# au-ar.net
KiCad netlist of a schematic drawn in EAGLE
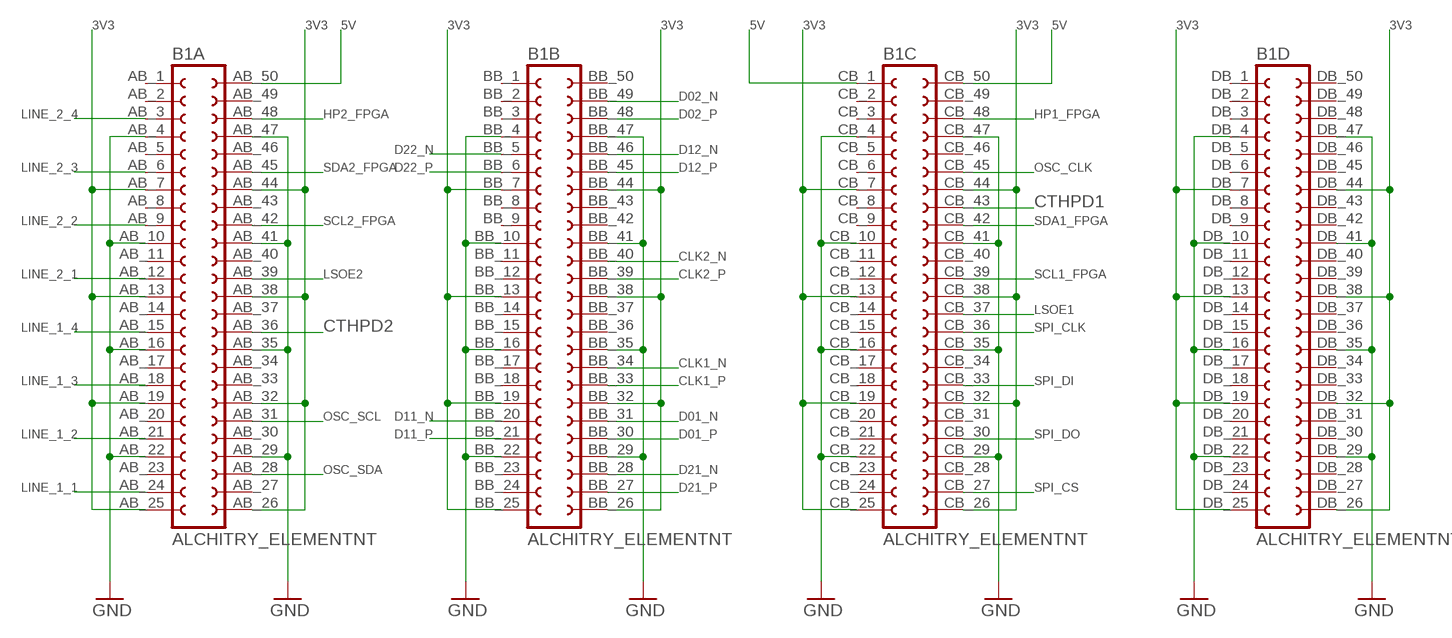
[diagram p0: schematic, sheet 1]
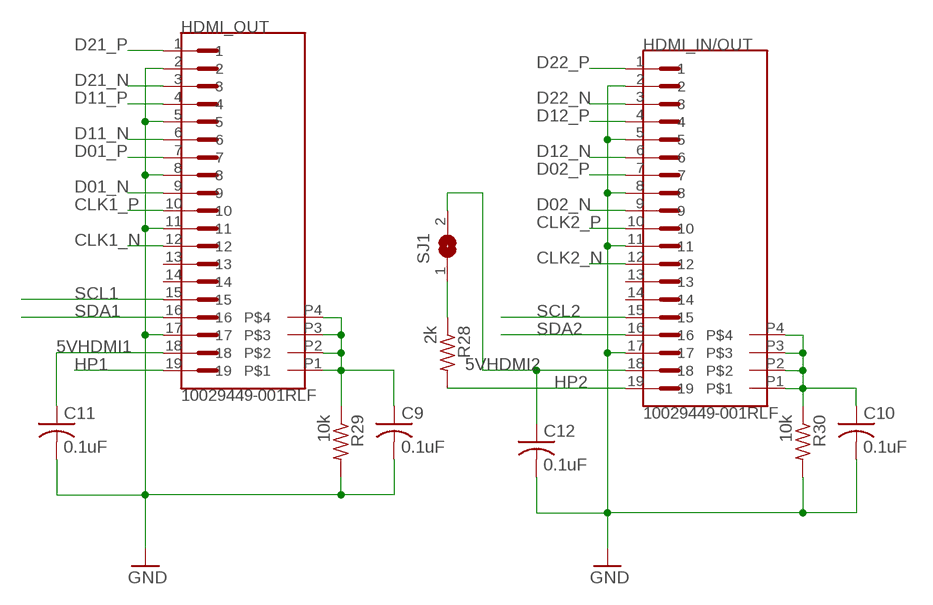
[diagram p1: schematic, sheet 2]
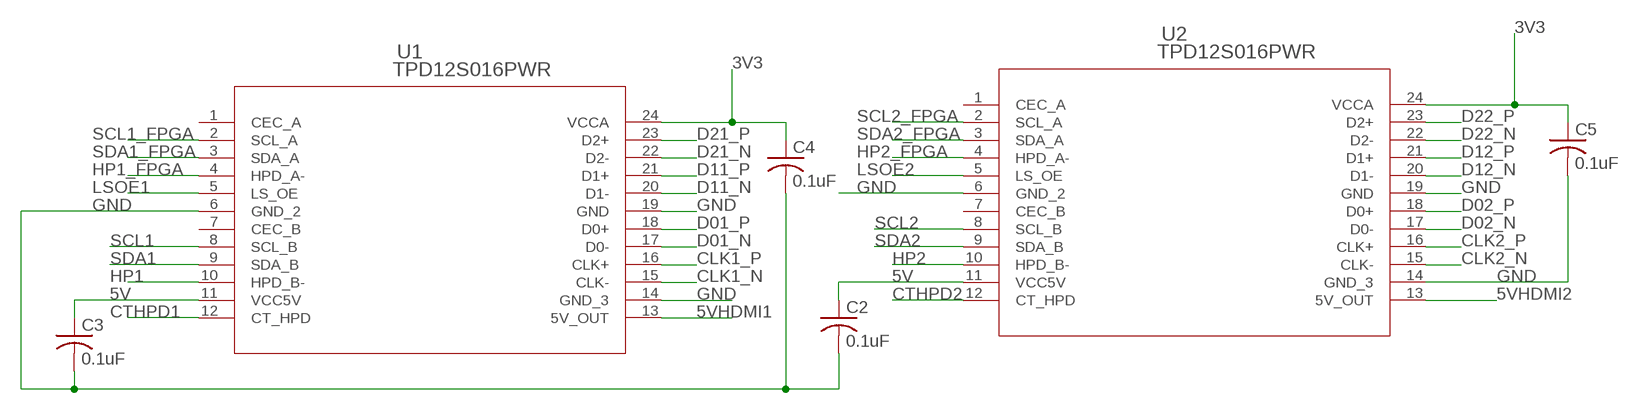
[diagram p2: schematic, sheet 3]
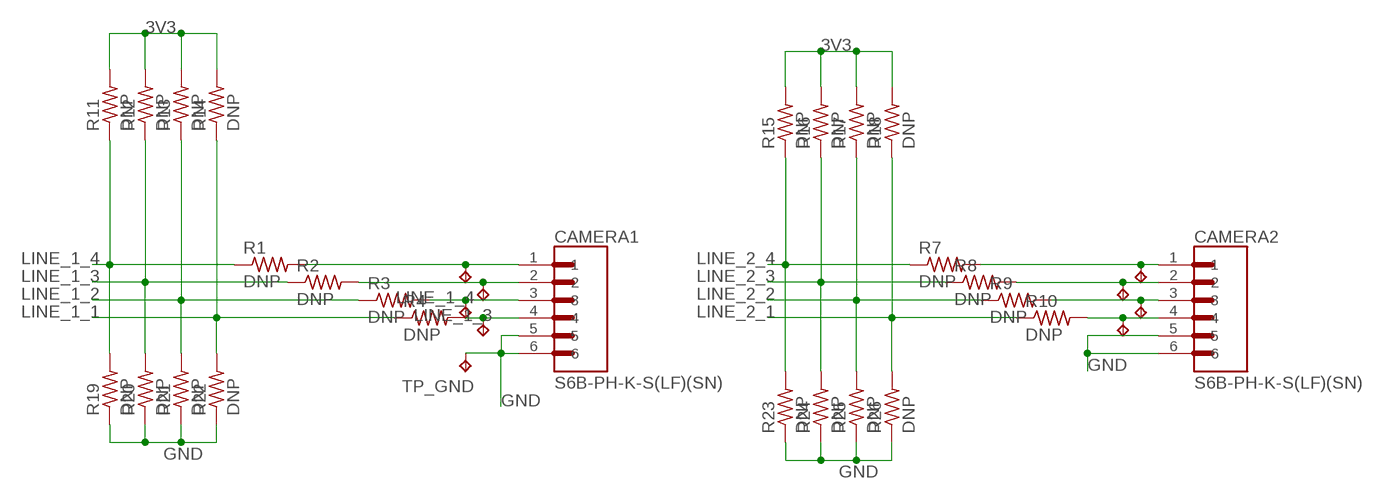
[diagram p3: schematic, sheet 4]
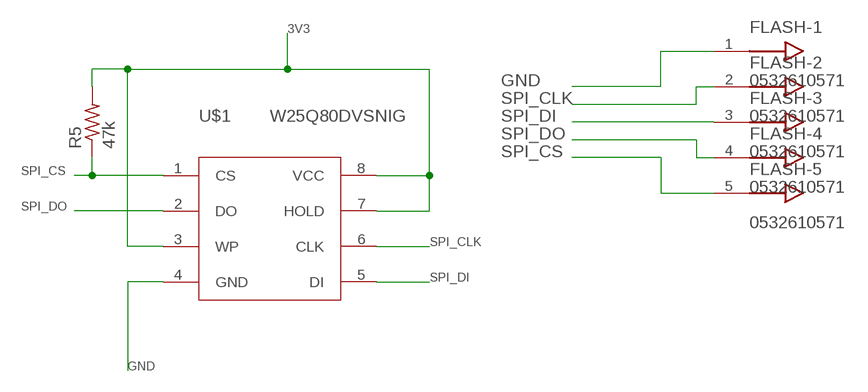
[diagram p4: schematic, sheet 5]
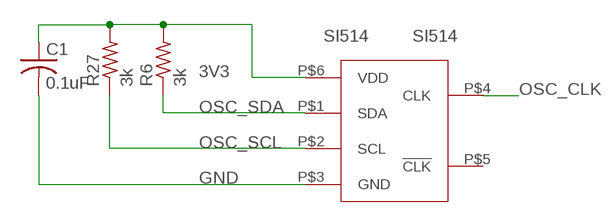
[diagram p5: schematic, sheet 6]

(export (version "E")
  (design (tool "Eeschema 10.0.6"))
  (components
    (comp (ref "C1")
      (value "0.1uF")
      (footprint "eagle-import:C0603")
      (libsource (lib "eagle-import") (part "C-USC0603"))
    )
    (comp (ref "R6")
      (value "3k")
      (footprint "eagle-import:R0603")
      (libsource (lib "eagle-import") (part "R-US_R0603"))
    )
    (comp (ref "R27")
      (value "3k")
      (footprint "eagle-import:R0603")
      (libsource (lib "eagle-import") (part "R-US_R0603"))
    )
    (comp (ref "SI514")
      (value "SI514")
      (footprint "eagle-import:XTAL-6PIN")
      (libsource (lib "eagle-import") (part "SI514"))
    )
    (comp (ref "FLASH")
      (value "0532610571")
      (footprint "eagle-import:PICOBLADE53261-0571")
      (fields (field (name "MANUFACTURER") "Molex Inc"))
      (libsource (lib "eagle-import") (part "0532610571"))
    )
    (comp (ref "R5")
      (value "47k")
      (footprint "eagle-import:R0603")
      (libsource (lib "eagle-import") (part "R-US_R0603"))
    )
    (comp (ref "U$1")
      (value "W25Q80DVSNIG")
      (footprint "eagle-import:SOIC8")
      (libsource (lib "eagle-import") (part "W25Q80DVSNIG"))
    )
    (comp (ref "C9")
      (value "0.1uF")
      (footprint "eagle-import:C0603")
      (libsource (lib "eagle-import") (part "C-USC0603"))
    )
    (comp (ref "C10")
      (value "0.1uF")
      (footprint "eagle-import:C0603")
      (libsource (lib "eagle-import") (part "C-USC0603"))
    )
    (comp (ref "C11")
      (value "0.1uF")
      (footprint "eagle-import:C0603")
      (libsource (lib "eagle-import") (part "C-USC0603"))
    )
    (comp (ref "C12")
      (value "0.1uF")
      (footprint "eagle-import:C0603")
      (libsource (lib "eagle-import") (part "C-USC0603"))
    )
    (comp (ref "HDMI_IN/OUT")
      (value "10029449-001RLF")
      (footprint "eagle-import:FCI_10029449-001RLF")
      (fields (field (name "MF") "Amphenol FCI"))
      (libsource (lib "eagle-import") (part "10029449-001RLF"))
    )
    (comp (ref "HDMI_OUT")
      (value "10029449-001RLF")
      (footprint "eagle-import:FCI_10029449-001RLF")
      (fields (field (name "MF") "Amphenol FCI"))
      (libsource (lib "eagle-import") (part "10029449-001RLF"))
    )
    (comp (ref "R28")
      (value "2k")
      (footprint "eagle-import:R0603")
      (libsource (lib "eagle-import") (part "R-US_R0603"))
    )
    (comp (ref "R29")
      (value "10k")
      (footprint "eagle-import:R0603")
      (libsource (lib "eagle-import") (part "R-US_R0603"))
    )
    (comp (ref "R30")
      (value "10k")
      (footprint "eagle-import:R0603")
      (libsource (lib "eagle-import") (part "R-US_R0603"))
    )
    (comp (ref "SJ1") (value "SJ") (footprint "eagle-import:SJ") (libsource (lib "eagle-import") (part "SJ")))
    (comp (ref "C2")
      (value "0.1uF")
      (footprint "eagle-import:C0603")
      (libsource (lib "eagle-import") (part "C-USC0603"))
    )
    (comp (ref "C3")
      (value "0.1uF")
      (footprint "eagle-import:C0603")
      (libsource (lib "eagle-import") (part "C-USC0603"))
    )
    (comp (ref "C4")
      (value "0.1uF")
      (footprint "eagle-import:C0603")
      (libsource (lib "eagle-import") (part "C-USC0603"))
    )
    (comp (ref "C5")
      (value "0.1uF")
      (footprint "eagle-import:C0603")
      (libsource (lib "eagle-import") (part "C-USC0603"))
    )
    (comp (ref "U1")
      (value "TPD12S016PWR")
      (footprint "eagle-import:PW24")
      (libsource (lib "eagle-import") (part "TPD12S016PWR"))
    )
    (comp (ref "U2")
      (value "TPD12S016PWR")
      (footprint "eagle-import:PW24")
      (libsource (lib "eagle-import") (part "TPD12S016PWR"))
    )
    (comp (ref "1")
      (value "LINE_1")
      (footprint "eagle-import:TP16R")
      (libsource (lib "eagle-import") (part "TPTP16R"))
    )
    (comp (ref "2")
      (value "LINE_2")
      (footprint "eagle-import:TP16R")
      (libsource (lib "eagle-import") (part "TPTP16R"))
    )
    (comp (ref "3")
      (value "LINE_3")
      (footprint "eagle-import:TP16R")
      (libsource (lib "eagle-import") (part "TPTP16R"))
    )
    (comp (ref "4")
      (value "LINE_1")
      (footprint "eagle-import:TP16R")
      (libsource (lib "eagle-import") (part "TPTP16R"))
    )
    (comp (ref "CAMERA1")
      (value "S6B-PH-K-S(LF)(SN)")
      (footprint "eagle-import:JST_S6B-PH-K-S(LF)(SN)")
      (fields
        (field (name "DIGI-KEY_PART_NUMBER") "455-1723-ND")
        (field (name "MF") "JST Sales")
        (field (name "MP") "S6B-PH-K-S_LF__SN_")
      )
      (libsource (lib "eagle-import") (part "S6B-PH-K-S(LF)(SN)"))
    )
    (comp (ref "CAMERA2")
      (value "S6B-PH-K-S(LF)(SN)")
      (footprint "eagle-import:JST_S6B-PH-K-S(LF)(SN)")
      (fields
        (field (name "DIGI-KEY_PART_NUMBER") "455-1723-ND")
        (field (name "MF") "JST Sales")
        (field (name "MP") "S6B-PH-K-S_LF__SN_")
      )
      (libsource (lib "eagle-import") (part "S6B-PH-K-S(LF)(SN)"))
    )
    (comp (ref "LINE_1_1")
      (value "TPTP16R")
      (footprint "eagle-import:TP16R")
      (libsource (lib "eagle-import") (part "TPTP16R"))
    )
    (comp (ref "LINE_1_2")
      (value "TPTP16R")
      (footprint "eagle-import:TP16R")
      (libsource (lib "eagle-import") (part "TPTP16R"))
    )
    (comp (ref "LINE_1_3")
      (value "TPTP16R")
      (footprint "eagle-import:TP16R")
      (libsource (lib "eagle-import") (part "TPTP16R"))
    )
    (comp (ref "LINE_1_4")
      (value "TPTP16R")
      (footprint "eagle-import:TP16R")
      (libsource (lib "eagle-import") (part "TPTP16R"))
    )
    (comp (ref "R1")
      (value "DNP")
      (footprint "eagle-import:R0603")
      (libsource (lib "eagle-import") (part "R-US_R0603"))
    )
    (comp (ref "R2")
      (value "DNP")
      (footprint "eagle-import:R0603")
      (libsource (lib "eagle-import") (part "R-US_R0603"))
    )
    (comp (ref "R3")
      (value "DNP")
      (footprint "eagle-import:R0603")
      (libsource (lib "eagle-import") (part "R-US_R0603"))
    )
    (comp (ref "R4")
      (value "DNP")
      (footprint "eagle-import:R0603")
      (libsource (lib "eagle-import") (part "R-US_R0603"))
    )
    (comp (ref "R7")
      (value "DNP")
      (footprint "eagle-import:R0603")
      (libsource (lib "eagle-import") (part "R-US_R0603"))
    )
    (comp (ref "R8")
      (value "DNP")
      (footprint "eagle-import:R0603")
      (libsource (lib "eagle-import") (part "R-US_R0603"))
    )
    (comp (ref "R9")
      (value "DNP")
      (footprint "eagle-import:R0603")
      (libsource (lib "eagle-import") (part "R-US_R0603"))
    )
    (comp (ref "R10")
      (value "DNP")
      (footprint "eagle-import:R0603")
      (libsource (lib "eagle-import") (part "R-US_R0603"))
    )
    (comp (ref "R11")
      (value "DNP")
      (footprint "eagle-import:R0603")
      (libsource (lib "eagle-import") (part "R-US_R0603"))
    )
    (comp (ref "R12")
      (value "DNP")
      (footprint "eagle-import:R0603")
      (libsource (lib "eagle-import") (part "R-US_R0603"))
    )
    (comp (ref "R13")
      (value "DNP")
      (footprint "eagle-import:R0603")
      (libsource (lib "eagle-import") (part "R-US_R0603"))
    )
    (comp (ref "R14")
      (value "DNP")
      (footprint "eagle-import:R0603")
      (libsource (lib "eagle-import") (part "R-US_R0603"))
    )
    (comp (ref "R15")
      (value "DNP")
      (footprint "eagle-import:R0603")
      (libsource (lib "eagle-import") (part "R-US_R0603"))
    )
    (comp (ref "R16")
      (value "DNP")
      (footprint "eagle-import:R0603")
      (libsource (lib "eagle-import") (part "R-US_R0603"))
    )
    (comp (ref "R17")
      (value "DNP")
      (footprint "eagle-import:R0603")
      (libsource (lib "eagle-import") (part "R-US_R0603"))
    )
    (comp (ref "R18")
      (value "DNP")
      (footprint "eagle-import:R0603")
      (libsource (lib "eagle-import") (part "R-US_R0603"))
    )
    (comp (ref "R19")
      (value "DNP")
      (footprint "eagle-import:R0603")
      (libsource (lib "eagle-import") (part "R-US_R0603"))
    )
    (comp (ref "R20")
      (value "DNP")
      (footprint "eagle-import:R0603")
      (libsource (lib "eagle-import") (part "R-US_R0603"))
    )
    (comp (ref "R21")
      (value "DNP")
      (footprint "eagle-import:R0603")
      (libsource (lib "eagle-import") (part "R-US_R0603"))
    )
    (comp (ref "R22")
      (value "DNP")
      (footprint "eagle-import:R0603")
      (libsource (lib "eagle-import") (part "R-US_R0603"))
    )
    (comp (ref "R23")
      (value "DNP")
      (footprint "eagle-import:R0603")
      (libsource (lib "eagle-import") (part "R-US_R0603"))
    )
    (comp (ref "R24")
      (value "DNP")
      (footprint "eagle-import:R0603")
      (libsource (lib "eagle-import") (part "R-US_R0603"))
    )
    (comp (ref "R25")
      (value "DNP")
      (footprint "eagle-import:R0603")
      (libsource (lib "eagle-import") (part "R-US_R0603"))
    )
    (comp (ref "R26")
      (value "DNP")
      (footprint "eagle-import:R0603")
      (libsource (lib "eagle-import") (part "R-US_R0603"))
    )
    (comp (ref "TP_GND")
      (value "TPTP16R")
      (footprint "eagle-import:TP16R")
      (libsource (lib "eagle-import") (part "TPTP16R"))
    )
    (comp (ref "B1")
      (value "ALCHITRY_ELEMENTNT")
      (footprint "eagle-import:ELEMENT_NO_TOP")
      (libsource (lib "eagle-import") (part "ALCHITRY_ELEMENTNT"))
    )
  )
  (nets
    (net (code "1") (name "3V3") (class "Default")
      (node (ref "B1") (pin "AB_13") (pinfunction "13_AB_13") (pintype "passive"))
      (node (ref "B1") (pin "AB_19") (pinfunction "19_AB_19") (pintype "passive"))
      (node (ref "B1") (pin "AB_25") (pinfunction "25_AB_25") (pintype "passive"))
      (node (ref "B1") (pin "AB_26") (pinfunction "26_AB_26") (pintype "passive"))
      (node (ref "B1") (pin "AB_32") (pinfunction "32_AB_32") (pintype "passive"))
      (node (ref "B1") (pin "AB_38") (pinfunction "38_AB_38") (pintype "passive"))
      (node (ref "B1") (pin "AB_44") (pinfunction "44_AB_44") (pintype "passive"))
      (node (ref "B1") (pin "AB_7") (pinfunction "7_AB_7") (pintype "passive"))
      (node (ref "B1") (pin "BB_13") (pinfunction "13_BB_13") (pintype "passive"))
      (node (ref "B1") (pin "BB_19") (pinfunction "19_BB_19") (pintype "passive"))
      (node (ref "B1") (pin "BB_25") (pinfunction "25_BB_25") (pintype "passive"))
      (node (ref "B1") (pin "BB_26") (pinfunction "26_BB_26") (pintype "passive"))
      (node (ref "B1") (pin "BB_32") (pinfunction "32_BB_32") (pintype "passive"))
      (node (ref "B1") (pin "BB_38") (pinfunction "38_BB_38") (pintype "passive"))
      (node (ref "B1") (pin "BB_44") (pinfunction "44_BB_44") (pintype "passive"))
      (node (ref "B1") (pin "BB_7") (pinfunction "7_BB_7") (pintype "passive"))
      (node (ref "B1") (pin "CB_13") (pinfunction "13_CB_13") (pintype "passive"))
      (node (ref "B1") (pin "CB_19") (pinfunction "19_CB_19") (pintype "passive"))
      (node (ref "B1") (pin "CB_25") (pinfunction "25_CB_25") (pintype "passive"))
      (node (ref "B1") (pin "CB_26") (pinfunction "26_CB_26") (pintype "passive"))
      (node (ref "B1") (pin "CB_32") (pinfunction "32_CB_32") (pintype "passive"))
      (node (ref "B1") (pin "CB_38") (pinfunction "38_CB_38") (pintype "passive"))
      (node (ref "B1") (pin "CB_44") (pinfunction "44_CB_44") (pintype "passive"))
      (node (ref "B1") (pin "CB_7") (pinfunction "7_CB_7") (pintype "passive"))
      (node (ref "B1") (pin "DB_13") (pinfunction "13_DB_13") (pintype "passive"))
      (node (ref "B1") (pin "DB_19") (pinfunction "19_DB_19") (pintype "passive"))
      (node (ref "B1") (pin "DB_25") (pinfunction "25_DB_25") (pintype "passive"))
      (node (ref "B1") (pin "DB_26") (pinfunction "26_DB_26") (pintype "passive"))
      (node (ref "B1") (pin "DB_32") (pinfunction "32_DB_32") (pintype "passive"))
      (node (ref "B1") (pin "DB_38") (pinfunction "38_DB_38") (pintype "passive"))
      (node (ref "B1") (pin "DB_44") (pinfunction "44_DB_44") (pintype "passive"))
      (node (ref "B1") (pin "DB_7") (pinfunction "7_DB_7") (pintype "passive"))
      (node (ref "C1") (pin "1") (pinfunction "1_1") (pintype "passive"))
      (node (ref "C4") (pin "1") (pinfunction "1_1") (pintype "passive"))
      (node (ref "C5") (pin "1") (pinfunction "1_1") (pintype "passive"))
      (node (ref "R11") (pin "2") (pinfunction "2_2") (pintype "passive"))
      (node (ref "R12") (pin "2") (pinfunction "2_2") (pintype "passive"))
      (node (ref "R13") (pin "2") (pinfunction "2_2") (pintype "passive"))
      (node (ref "R14") (pin "2") (pinfunction "2_2") (pintype "passive"))
      (node (ref "R15") (pin "2") (pinfunction "2_2") (pintype "passive"))
      (node (ref "R16") (pin "2") (pinfunction "2_2") (pintype "passive"))
      (node (ref "R17") (pin "2") (pinfunction "2_2") (pintype "passive"))
      (node (ref "R18") (pin "2") (pinfunction "2_2") (pintype "passive"))
      (node (ref "R27") (pin "2") (pinfunction "2_2") (pintype "passive"))
      (node (ref "R5") (pin "2") (pinfunction "2_2") (pintype "passive"))
      (node (ref "R6") (pin "2") (pinfunction "2_2") (pintype "passive"))
      (node (ref "SI514") (pin "P$6") (pinfunction "VDD_P$6") (pintype "bidirectional"))
      (node (ref "U$1") (pin "3") (pinfunction "WP_3") (pintype "bidirectional"))
      (node (ref "U$1") (pin "7") (pinfunction "HOLD_7") (pintype "bidirectional"))
      (node (ref "U$1") (pin "8") (pinfunction "VCC_8") (pintype "bidirectional"))
      (node (ref "U1") (pin "24") (pinfunction "VCCA_24") (pintype "power_in"))
      (node (ref "U2") (pin "24") (pinfunction "VCCA_24") (pintype "power_in"))
    )
    (net (code "2") (name "5V") (class "Default")
      (node (ref "B1") (pin "AB_50") (pinfunction "50_AB_50") (pintype "passive"))
      (node (ref "B1") (pin "CB_1") (pinfunction "1_CB_1") (pintype "passive"))
      (node (ref "B1") (pin "CB_50") (pinfunction "50_CB_50") (pintype "passive"))
      (node (ref "C2") (pin "1") (pinfunction "1_1") (pintype "passive"))
      (node (ref "C3") (pin "1") (pinfunction "1_1") (pintype "passive"))
      (node (ref "U1") (pin "11") (pinfunction "VCC5V_11") (pintype "power_in"))
      (node (ref "U2") (pin "11") (pinfunction "VCC5V_11") (pintype "power_in"))
    )
    (net (code "3") (name "5VHDMI1") (class "Default")
      (node (ref "C11") (pin "1") (pinfunction "1_1") (pintype "passive"))
      (node (ref "HDMI_OUT") (pin "18") (pinfunction "18_18") (pintype "passive"))
      (node (ref "U1") (pin "13") (pinfunction "5V_OUT_13") (pintype "output"))
    )
    (net (code "4") (name "5VHDMI2") (class "Default")
      (node (ref "C12") (pin "1") (pinfunction "1_1") (pintype "passive"))
      (node (ref "HDMI_IN/OUT") (pin "18") (pinfunction "18_18") (pintype "passive"))
      (node (ref "SJ1") (pin "2") (pinfunction "2_2") (pintype "passive"))
      (node (ref "U2") (pin "13") (pinfunction "5V_OUT_13") (pintype "output"))
    )
    (net (code "5") (name "CLK1_N") (class "Default")
      (node (ref "B1") (pin "BB_34") (pinfunction "34_BB_34") (pintype "passive"))
      (node (ref "HDMI_OUT") (pin "12") (pinfunction "12_12") (pintype "passive"))
      (node (ref "U1") (pin "15") (pinfunction "CLK-_15") (pintype "passive"))
    )
    (net (code "6") (name "CLK1_P") (class "Default")
      (node (ref "B1") (pin "BB_33") (pinfunction "33_BB_33") (pintype "passive"))
      (node (ref "HDMI_OUT") (pin "10") (pinfunction "10_10") (pintype "passive"))
      (node (ref "U1") (pin "16") (pinfunction "CLK+_16") (pintype "passive"))
    )
    (net (code "7") (name "CLK2_N") (class "Default")
      (node (ref "B1") (pin "BB_40") (pinfunction "40_BB_40") (pintype "passive"))
      (node (ref "HDMI_IN/OUT") (pin "12") (pinfunction "12_12") (pintype "passive"))
      (node (ref "U2") (pin "15") (pinfunction "CLK-_15") (pintype "passive"))
    )
    (net (code "8") (name "CLK2_P") (class "Default")
      (node (ref "B1") (pin "BB_39") (pinfunction "39_BB_39") (pintype "passive"))
      (node (ref "HDMI_IN/OUT") (pin "10") (pinfunction "10_10") (pintype "passive"))
      (node (ref "U2") (pin "16") (pinfunction "CLK+_16") (pintype "passive"))
    )
    (net (code "9") (name "CTHPD1") (class "Default")
      (node (ref "B1") (pin "CB_43") (pinfunction "43_CB_43") (pintype "passive"))
      (node (ref "U1") (pin "12") (pinfunction "CT_HPD_12") (pintype "input"))
    )
    (net (code "10") (name "CTHPD2") (class "Default")
      (node (ref "B1") (pin "AB_36") (pinfunction "36_AB_36") (pintype "passive"))
      (node (ref "U2") (pin "12") (pinfunction "CT_HPD_12") (pintype "input"))
    )
    (net (code "11") (name "D01_N") (class "Default")
      (node (ref "B1") (pin "BB_31") (pinfunction "31_BB_31") (pintype "passive"))
      (node (ref "HDMI_OUT") (pin "9") (pinfunction "9_9") (pintype "passive"))
      (node (ref "U1") (pin "17") (pinfunction "D0-_17") (pintype "passive"))
    )
    (net (code "12") (name "D01_P") (class "Default")
      (node (ref "B1") (pin "BB_30") (pinfunction "30_BB_30") (pintype "passive"))
      (node (ref "HDMI_OUT") (pin "7") (pinfunction "7_7") (pintype "passive"))
      (node (ref "U1") (pin "18") (pinfunction "D0+_18") (pintype "passive"))
    )
    (net (code "13") (name "D02_N") (class "Default")
      (node (ref "B1") (pin "BB_49") (pinfunction "49_BB_49") (pintype "passive"))
      (node (ref "HDMI_IN/OUT") (pin "9") (pinfunction "9_9") (pintype "passive"))
      (node (ref "U2") (pin "17") (pinfunction "D0-_17") (pintype "passive"))
    )
    (net (code "14") (name "D02_P") (class "Default")
      (node (ref "B1") (pin "BB_48") (pinfunction "48_BB_48") (pintype "passive"))
      (node (ref "HDMI_IN/OUT") (pin "7") (pinfunction "7_7") (pintype "passive"))
      (node (ref "U2") (pin "18") (pinfunction "D0+_18") (pintype "passive"))
    )
    (net (code "15") (name "D11_N") (class "Default")
      (node (ref "B1") (pin "BB_20") (pinfunction "20_BB_20") (pintype "passive"))
      (node (ref "HDMI_OUT") (pin "6") (pinfunction "6_6") (pintype "passive"))
      (node (ref "U1") (pin "20") (pinfunction "D1-_20") (pintype "passive"))
    )
    (net (code "16") (name "D11_P") (class "Default")
      (node (ref "B1") (pin "BB_21") (pinfunction "21_BB_21") (pintype "passive"))
      (node (ref "HDMI_OUT") (pin "4") (pinfunction "4_4") (pintype "passive"))
      (node (ref "U1") (pin "21") (pinfunction "D1+_21") (pintype "passive"))
    )
    (net (code "17") (name "D12_N") (class "Default")
      (node (ref "B1") (pin "BB_46") (pinfunction "46_BB_46") (pintype "passive"))
      (node (ref "HDMI_IN/OUT") (pin "6") (pinfunction "6_6") (pintype "passive"))
      (node (ref "U2") (pin "20") (pinfunction "D1-_20") (pintype "passive"))
    )
    (net (code "18") (name "D12_P") (class "Default")
      (node (ref "B1") (pin "BB_45") (pinfunction "45_BB_45") (pintype "passive"))
      (node (ref "HDMI_IN/OUT") (pin "4") (pinfunction "4_4") (pintype "passive"))
      (node (ref "U2") (pin "21") (pinfunction "D1+_21") (pintype "passive"))
    )
    (net (code "19") (name "D21_N") (class "Default")
      (node (ref "B1") (pin "BB_28") (pinfunction "28_BB_28") (pintype "passive"))
      (node (ref "HDMI_OUT") (pin "3") (pinfunction "3_3") (pintype "passive"))
      (node (ref "U1") (pin "22") (pinfunction "D2-_22") (pintype "passive"))
    )
    (net (code "20") (name "D21_P") (class "Default")
      (node (ref "B1") (pin "BB_27") (pinfunction "27_BB_27") (pintype "passive"))
      (node (ref "HDMI_OUT") (pin "1") (pinfunction "1_1") (pintype "passive"))
      (node (ref "U1") (pin "23") (pinfunction "D2+_23") (pintype "passive"))
    )
    (net (code "21") (name "D22_N") (class "Default")
      (node (ref "B1") (pin "BB_5") (pinfunction "5_BB_5") (pintype "passive"))
      (node (ref "HDMI_IN/OUT") (pin "3") (pinfunction "3_3") (pintype "passive"))
      (node (ref "U2") (pin "22") (pinfunction "D2-_22") (pintype "passive"))
    )
    (net (code "22") (name "D22_P") (class "Default")
      (node (ref "B1") (pin "BB_6") (pinfunction "6_BB_6") (pintype "passive"))
      (node (ref "HDMI_IN/OUT") (pin "1") (pinfunction "1_1") (pintype "passive"))
      (node (ref "U2") (pin "23") (pinfunction "D2+_23") (pintype "passive"))
    )
    (net (code "23") (name "GND") (class "Default")
      (node (ref "B1") (pin "AB_10") (pinfunction "10_AB_10") (pintype "passive"))
      (node (ref "B1") (pin "AB_16") (pinfunction "16_AB_16") (pintype "passive"))
      (node (ref "B1") (pin "AB_22") (pinfunction "22_AB_22") (pintype "passive"))
      (node (ref "B1") (pin "AB_29") (pinfunction "29_AB_29") (pintype "passive"))
      (node (ref "B1") (pin "AB_35") (pinfunction "35_AB_35") (pintype "passive"))
      (node (ref "B1") (pin "AB_4") (pinfunction "4_AB_4") (pintype "passive"))
      (node (ref "B1") (pin "AB_41") (pinfunction "41_AB_41") (pintype "passive"))
      (node (ref "B1") (pin "AB_47") (pinfunction "47_AB_47") (pintype "passive"))
      (node (ref "B1") (pin "BB_10") (pinfunction "10_BB_10") (pintype "passive"))
      (node (ref "B1") (pin "BB_16") (pinfunction "16_BB_16") (pintype "passive"))
      (node (ref "B1") (pin "BB_22") (pinfunction "22_BB_22") (pintype "passive"))
      (node (ref "B1") (pin "BB_29") (pinfunction "29_BB_29") (pintype "passive"))
      (node (ref "B1") (pin "BB_35") (pinfunction "35_BB_35") (pintype "passive"))
      (node (ref "B1") (pin "BB_4") (pinfunction "4_BB_4") (pintype "passive"))
      (node (ref "B1") (pin "BB_41") (pinfunction "41_BB_41") (pintype "passive"))
      (node (ref "B1") (pin "BB_47") (pinfunction "47_BB_47") (pintype "passive"))
      (node (ref "B1") (pin "CB_10") (pinfunction "10_CB_10") (pintype "passive"))
      (node (ref "B1") (pin "CB_16") (pinfunction "16_CB_16") (pintype "passive"))
      (node (ref "B1") (pin "CB_22") (pinfunction "22_CB_22") (pintype "passive"))
      (node (ref "B1") (pin "CB_29") (pinfunction "29_CB_29") (pintype "passive"))
      (node (ref "B1") (pin "CB_35") (pinfunction "35_CB_35") (pintype "passive"))
      (node (ref "B1") (pin "CB_4") (pinfunction "4_CB_4") (pintype "passive"))
      (node (ref "B1") (pin "CB_41") (pinfunction "41_CB_41") (pintype "passive"))
      (node (ref "B1") (pin "CB_47") (pinfunction "47_CB_47") (pintype "passive"))
      (node (ref "B1") (pin "DB_10") (pinfunction "10_DB_10") (pintype "passive"))
      (node (ref "B1") (pin "DB_16") (pinfunction "16_DB_16") (pintype "passive"))
      (node (ref "B1") (pin "DB_22") (pinfunction "22_DB_22") (pintype "passive"))
      (node (ref "B1") (pin "DB_29") (pinfunction "29_DB_29") (pintype "passive"))
      (node (ref "B1") (pin "DB_35") (pinfunction "35_DB_35") (pintype "passive"))
      (node (ref "B1") (pin "DB_4") (pinfunction "4_DB_4") (pintype "passive"))
      (node (ref "B1") (pin "DB_41") (pinfunction "41_DB_41") (pintype "passive"))
      (node (ref "B1") (pin "DB_47") (pinfunction "47_DB_47") (pintype "passive"))
      (node (ref "C1") (pin "2") (pinfunction "2_2") (pintype "passive"))
      (node (ref "C10") (pin "2") (pinfunction "2_2") (pintype "passive"))
      (node (ref "C11") (pin "2") (pinfunction "2_2") (pintype "passive"))
      (node (ref "C12") (pin "2") (pinfunction "2_2") (pintype "passive"))
      (node (ref "C2") (pin "2") (pinfunction "2_2") (pintype "passive"))
      (node (ref "C3") (pin "2") (pinfunction "2_2") (pintype "passive"))
      (node (ref "C4") (pin "2") (pinfunction "2_2") (pintype "passive"))
      (node (ref "C5") (pin "2") (pinfunction "2_2") (pintype "passive"))
      (node (ref "C9") (pin "2") (pinfunction "2_2") (pintype "passive"))
      (node (ref "CAMERA1") (pin "5") (pinfunction "5_5") (pintype "passive"))
      (node (ref "CAMERA1") (pin "6") (pinfunction "6_6") (pintype "passive"))
      (node (ref "CAMERA2") (pin "5") (pinfunction "5_5") (pintype "passive"))
      (node (ref "CAMERA2") (pin "6") (pinfunction "6_6") (pintype "passive"))
      (node (ref "FLASH") (pin "1") (pinfunction "P$1_1") (pintype "bidirectional"))
      (node (ref "HDMI_IN/OUT") (pin "11") (pinfunction "11_11") (pintype "passive"))
      (node (ref "HDMI_IN/OUT") (pin "17") (pinfunction "17_17") (pintype "passive"))
      (node (ref "HDMI_IN/OUT") (pin "2") (pinfunction "2_2") (pintype "passive"))
      (node (ref "HDMI_IN/OUT") (pin "5") (pinfunction "5_5") (pintype "passive"))
      (node (ref "HDMI_IN/OUT") (pin "8") (pinfunction "8_8") (pintype "passive"))
      (node (ref "HDMI_OUT") (pin "11") (pinfunction "11_11") (pintype "passive"))
      (node (ref "HDMI_OUT") (pin "17") (pinfunction "17_17") (pintype "passive"))
      (node (ref "HDMI_OUT") (pin "2") (pinfunction "2_2") (pintype "passive"))
      (node (ref "HDMI_OUT") (pin "5") (pinfunction "5_5") (pintype "passive"))
      (node (ref "HDMI_OUT") (pin "8") (pinfunction "8_8") (pintype "passive"))
      (node (ref "R19") (pin "1") (pinfunction "1_1") (pintype "passive"))
      (node (ref "R20") (pin "1") (pinfunction "1_1") (pintype "passive"))
      (node (ref "R21") (pin "1") (pinfunction "1_1") (pintype "passive"))
      (node (ref "R22") (pin "1") (pinfunction "1_1") (pintype "passive"))
      (node (ref "R23") (pin "1") (pinfunction "1_1") (pintype "passive"))
      (node (ref "R24") (pin "1") (pinfunction "1_1") (pintype "passive"))
      (node (ref "R25") (pin "1") (pinfunction "1_1") (pintype "passive"))
      (node (ref "R26") (pin "1") (pinfunction "1_1") (pintype "passive"))
      (node (ref "R29") (pin "2") (pinfunction "2_2") (pintype "passive"))
      (node (ref "R30") (pin "2") (pinfunction "2_2") (pintype "passive"))
      (node (ref "SI514") (pin "P$3") (pinfunction "GND_P$3") (pintype "bidirectional"))
      (node (ref "TP_GND") (pin "TP") (pinfunction "TP_TP") (pintype "input"))
      (node (ref "U$1") (pin "4") (pinfunction "GND_4") (pintype "bidirectional"))
      (node (ref "U1") (pin "14") (pinfunction "GND_3_14") (pintype "power_in"))
      (node (ref "U1") (pin "19") (pinfunction "GND_19") (pintype "power_in"))
      (node (ref "U1") (pin "6") (pinfunction "GND_2_6") (pintype "power_in"))
      (node (ref "U2") (pin "14") (pinfunction "GND_3_14") (pintype "power_in"))
      (node (ref "U2") (pin "19") (pinfunction "GND_19") (pintype "power_in"))
      (node (ref "U2") (pin "6") (pinfunction "GND_2_6") (pintype "power_in"))
    )
    (net (code "24") (name "HP1") (class "Default")
      (node (ref "HDMI_OUT") (pin "19") (pinfunction "19_19") (pintype "passive"))
      (node (ref "U1") (pin "10") (pinfunction "HPD_B-_10") (pintype "input"))
    )
    (net (code "25") (name "HP1_FPGA") (class "Default")
      (node (ref "B1") (pin "CB_48") (pinfunction "48_CB_48") (pintype "passive"))
      (node (ref "U1") (pin "4") (pinfunction "HPD_A-_4") (pintype "output"))
    )
    (net (code "26") (name "HP2") (class "Default")
      (node (ref "HDMI_IN/OUT") (pin "19") (pinfunction "19_19") (pintype "passive"))
      (node (ref "R28") (pin "2") (pinfunction "2_2") (pintype "passive"))
      (node (ref "U2") (pin "10") (pinfunction "HPD_B-_10") (pintype "input"))
    )
    (net (code "27") (name "HP2_FPGA") (class "Default")
      (node (ref "B1") (pin "AB_48") (pinfunction "48_AB_48") (pintype "passive"))
      (node (ref "U2") (pin "4") (pinfunction "HPD_A-_4") (pintype "output"))
    )
    (net (code "28") (name "LINE_1_1") (class "Default")
      (node (ref "B1") (pin "AB_24") (pinfunction "24_AB_24") (pintype "passive"))
      (node (ref "R14") (pin "1") (pinfunction "1_1") (pintype "passive"))
      (node (ref "R22") (pin "2") (pinfunction "2_2") (pintype "passive"))
      (node (ref "R4") (pin "1") (pinfunction "1_1") (pintype "passive"))
    )
    (net (code "29") (name "LINE_1_2") (class "Default")
      (node (ref "B1") (pin "AB_21") (pinfunction "21_AB_21") (pintype "passive"))
      (node (ref "R13") (pin "1") (pinfunction "1_1") (pintype "passive"))
      (node (ref "R21") (pin "2") (pinfunction "2_2") (pintype "passive"))
      (node (ref "R3") (pin "1") (pinfunction "1_1") (pintype "passive"))
    )
    (net (code "30") (name "LINE_1_3") (class "Default")
      (node (ref "B1") (pin "AB_18") (pinfunction "18_AB_18") (pintype "passive"))
      (node (ref "R12") (pin "1") (pinfunction "1_1") (pintype "passive"))
      (node (ref "R2") (pin "1") (pinfunction "1_1") (pintype "passive"))
      (node (ref "R20") (pin "2") (pinfunction "2_2") (pintype "passive"))
    )
    (net (code "31") (name "LINE_1_4") (class "Default")
      (node (ref "B1") (pin "AB_15") (pinfunction "15_AB_15") (pintype "passive"))
      (node (ref "R1") (pin "1") (pinfunction "1_1") (pintype "passive"))
      (node (ref "R11") (pin "1") (pinfunction "1_1") (pintype "passive"))
      (node (ref "R19") (pin "2") (pinfunction "2_2") (pintype "passive"))
    )
    (net (code "32") (name "LINE_2_1") (class "Default")
      (node (ref "B1") (pin "AB_12") (pinfunction "12_AB_12") (pintype "passive"))
      (node (ref "R10") (pin "1") (pinfunction "1_1") (pintype "passive"))
      (node (ref "R18") (pin "1") (pinfunction "1_1") (pintype "passive"))
      (node (ref "R26") (pin "2") (pinfunction "2_2") (pintype "passive"))
    )
    (net (code "33") (name "LINE_2_2") (class "Default")
      (node (ref "B1") (pin "AB_9") (pinfunction "9_AB_9") (pintype "passive"))
      (node (ref "R17") (pin "1") (pinfunction "1_1") (pintype "passive"))
      (node (ref "R25") (pin "2") (pinfunction "2_2") (pintype "passive"))
      (node (ref "R9") (pin "1") (pinfunction "1_1") (pintype "passive"))
    )
    (net (code "34") (name "LINE_2_3") (class "Default")
      (node (ref "B1") (pin "AB_6") (pinfunction "6_AB_6") (pintype "passive"))
      (node (ref "R16") (pin "1") (pinfunction "1_1") (pintype "passive"))
      (node (ref "R24") (pin "2") (pinfunction "2_2") (pintype "passive"))
      (node (ref "R8") (pin "1") (pinfunction "1_1") (pintype "passive"))
    )
    (net (code "35") (name "LINE_2_4") (class "Default")
      (node (ref "B1") (pin "AB_3") (pinfunction "3_AB_3") (pintype "passive"))
      (node (ref "R15") (pin "1") (pinfunction "1_1") (pintype "passive"))
      (node (ref "R23") (pin "2") (pinfunction "2_2") (pintype "passive"))
      (node (ref "R7") (pin "1") (pinfunction "1_1") (pintype "passive"))
    )
    (net (code "36") (name "LSOE1") (class "Default")
      (node (ref "B1") (pin "CB_37") (pinfunction "37_CB_37") (pintype "passive"))
      (node (ref "U1") (pin "5") (pinfunction "LS_OE_5") (pintype "input"))
    )
    (net (code "37") (name "LSOE2") (class "Default")
      (node (ref "B1") (pin "AB_39") (pinfunction "39_AB_39") (pintype "passive"))
      (node (ref "U2") (pin "5") (pinfunction "LS_OE_5") (pintype "input"))
    )
    (net (code "38") (name "Net-(1-PadTP)") (class "Default")
      (node (ref "1") (pin "TP") (pinfunction "TP_TP") (pintype "input"))
      (node (ref "CAMERA2") (pin "4") (pinfunction "4_4") (pintype "passive"))
      (node (ref "R10") (pin "2") (pinfunction "2_2") (pintype "passive"))
    )
    (net (code "39") (name "Net-(2-PadTP)") (class "Default")
      (node (ref "2") (pin "TP") (pinfunction "TP_TP") (pintype "input"))
      (node (ref "CAMERA2") (pin "3") (pinfunction "3_3") (pintype "passive"))
      (node (ref "R9") (pin "2") (pinfunction "2_2") (pintype "passive"))
    )
    (net (code "40") (name "Net-(3-PadTP)") (class "Default")
      (node (ref "3") (pin "TP") (pinfunction "TP_TP") (pintype "input"))
      (node (ref "CAMERA2") (pin "2") (pinfunction "2_2") (pintype "passive"))
      (node (ref "R8") (pin "2") (pinfunction "2_2") (pintype "passive"))
    )
    (net (code "41") (name "Net-(4-PadTP)") (class "Default")
      (node (ref "4") (pin "TP") (pinfunction "TP_TP") (pintype "input"))
      (node (ref "CAMERA2") (pin "1") (pinfunction "1_1") (pintype "passive"))
      (node (ref "R7") (pin "2") (pinfunction "2_2") (pintype "passive"))
    )
    (net (code "42") (name "Net-(CAMERA1-Pad1)") (class "Default")
      (node (ref "CAMERA1") (pin "1") (pinfunction "1_1") (pintype "passive"))
      (node (ref "LINE_1_4") (pin "TP") (pinfunction "TP_TP") (pintype "input"))
      (node (ref "R1") (pin "2") (pinfunction "2_2") (pintype "passive"))
    )
    (net (code "43") (name "Net-(CAMERA1-Pad2)") (class "Default")
      (node (ref "CAMERA1") (pin "2") (pinfunction "2_2") (pintype "passive"))
      (node (ref "LINE_1_3") (pin "TP") (pinfunction "TP_TP") (pintype "input"))
      (node (ref "R2") (pin "2") (pinfunction "2_2") (pintype "passive"))
    )
    (net (code "44") (name "Net-(CAMERA1-Pad3)") (class "Default")
      (node (ref "CAMERA1") (pin "3") (pinfunction "3_3") (pintype "passive"))
      (node (ref "LINE_1_2") (pin "TP") (pinfunction "TP_TP") (pintype "input"))
      (node (ref "R3") (pin "2") (pinfunction "2_2") (pintype "passive"))
    )
    (net (code "45") (name "Net-(CAMERA1-Pad4)") (class "Default")
      (node (ref "CAMERA1") (pin "4") (pinfunction "4_4") (pintype "passive"))
      (node (ref "LINE_1_1") (pin "TP") (pinfunction "TP_TP") (pintype "input"))
      (node (ref "R4") (pin "2") (pinfunction "2_2") (pintype "passive"))
    )
    (net (code "46") (name "Net-(HDMI_IN/OUT-P$1)") (class "Default")
      (node (ref "C10") (pin "1") (pinfunction "1_1") (pintype "passive"))
      (node (ref "HDMI_IN/OUT") (pin "P1") (pinfunction "P$1_P1") (pintype "bidirectional"))
      (node (ref "HDMI_IN/OUT") (pin "P2") (pinfunction "P$2_P2") (pintype "bidirectional"))
      (node (ref "HDMI_IN/OUT") (pin "P3") (pinfunction "P$3_P3") (pintype "bidirectional"))
      (node (ref "HDMI_IN/OUT") (pin "P4") (pinfunction "P$4_P4") (pintype "bidirectional"))
      (node (ref "R30") (pin "1") (pinfunction "1_1") (pintype "passive"))
    )
    (net (code "47") (name "Net-(HDMI_OUT-P$1)") (class "Default")
      (node (ref "C9") (pin "1") (pinfunction "1_1") (pintype "passive"))
      (node (ref "HDMI_OUT") (pin "P1") (pinfunction "P$1_P1") (pintype "bidirectional"))
      (node (ref "HDMI_OUT") (pin "P2") (pinfunction "P$2_P2") (pintype "bidirectional"))
      (node (ref "HDMI_OUT") (pin "P3") (pinfunction "P$3_P3") (pintype "bidirectional"))
      (node (ref "HDMI_OUT") (pin "P4") (pinfunction "P$4_P4") (pintype "bidirectional"))
      (node (ref "R29") (pin "1") (pinfunction "1_1") (pintype "passive"))
    )
    (net (code "48") (name "Net-(R28-Pad1)") (class "Default")
      (node (ref "R28") (pin "1") (pinfunction "1_1") (pintype "passive"))
      (node (ref "SJ1") (pin "1") (pinfunction "1_1") (pintype "passive"))
    )
    (net (code "49") (name "OSC_CLK") (class "Default")
      (node (ref "B1") (pin "CB_45") (pinfunction "45_CB_45") (pintype "passive"))
      (node (ref "SI514") (pin "P$4") (pinfunction "CLK_P$4") (pintype "bidirectional"))
    )
    (net (code "50") (name "OSC_SCL") (class "Default")
      (node (ref "B1") (pin "AB_31") (pinfunction "31_AB_31") (pintype "passive"))
      (node (ref "R27") (pin "1") (pinfunction "1_1") (pintype "passive"))
      (node (ref "SI514") (pin "P$2") (pinfunction "SCL_P$2") (pintype "bidirectional"))
    )
    (net (code "51") (name "OSC_SDA") (class "Default")
      (node (ref "B1") (pin "AB_28") (pinfunction "28_AB_28") (pintype "passive"))
      (node (ref "R6") (pin "1") (pinfunction "1_1") (pintype "passive"))
      (node (ref "SI514") (pin "P$1") (pinfunction "SDA_P$1") (pintype "bidirectional"))
    )
    (net (code "52") (name "SCL1") (class "Default")
      (node (ref "HDMI_OUT") (pin "15") (pinfunction "15_15") (pintype "passive"))
      (node (ref "U1") (pin "8") (pinfunction "SCL_B_8") (pintype "bidirectional"))
    )
    (net (code "53") (name "SCL1_FPGA") (class "Default")
      (node (ref "B1") (pin "CB_39") (pinfunction "39_CB_39") (pintype "passive"))
      (node (ref "U1") (pin "2") (pinfunction "SCL_A_2") (pintype "bidirectional"))
    )
    (net (code "54") (name "SCL2") (class "Default")
      (node (ref "HDMI_IN/OUT") (pin "15") (pinfunction "15_15") (pintype "passive"))
      (node (ref "U2") (pin "8") (pinfunction "SCL_B_8") (pintype "bidirectional"))
    )
    (net (code "55") (name "SCL2_FPGA") (class "Default")
      (node (ref "B1") (pin "AB_42") (pinfunction "42_AB_42") (pintype "passive"))
      (node (ref "U2") (pin "2") (pinfunction "SCL_A_2") (pintype "bidirectional"))
    )
    (net (code "56") (name "SDA1") (class "Default")
      (node (ref "HDMI_OUT") (pin "16") (pinfunction "16_16") (pintype "passive"))
      (node (ref "U1") (pin "9") (pinfunction "SDA_B_9") (pintype "bidirectional"))
    )
    (net (code "57") (name "SDA1_FPGA") (class "Default")
      (node (ref "B1") (pin "CB_42") (pinfunction "42_CB_42") (pintype "passive"))
      (node (ref "U1") (pin "3") (pinfunction "SDA_A_3") (pintype "bidirectional"))
    )
    (net (code "58") (name "SDA2") (class "Default")
      (node (ref "HDMI_IN/OUT") (pin "16") (pinfunction "16_16") (pintype "passive"))
      (node (ref "U2") (pin "9") (pinfunction "SDA_B_9") (pintype "bidirectional"))
    )
    (net (code "59") (name "SDA2_FPGA") (class "Default")
      (node (ref "B1") (pin "AB_45") (pinfunction "45_AB_45") (pintype "passive"))
      (node (ref "U2") (pin "3") (pinfunction "SDA_A_3") (pintype "bidirectional"))
    )
    (net (code "60") (name "SPI_CLK") (class "Default")
      (node (ref "B1") (pin "CB_36") (pinfunction "36_CB_36") (pintype "passive"))
      (node (ref "FLASH") (pin "2") (pinfunction "P$1_2") (pintype "bidirectional"))
      (node (ref "U$1") (pin "6") (pinfunction "CLK_6") (pintype "bidirectional"))
    )
    (net (code "61") (name "SPI_CS") (class "Default")
      (node (ref "B1") (pin "CB_27") (pinfunction "27_CB_27") (pintype "passive"))
      (node (ref "FLASH") (pin "5") (pinfunction "P$1_5") (pintype "bidirectional"))
      (node (ref "R5") (pin "1") (pinfunction "1_1") (pintype "passive"))
      (node (ref "U$1") (pin "1") (pinfunction "CS_1") (pintype "bidirectional"))
    )
    (net (code "62") (name "SPI_DI") (class "Default")
      (node (ref "B1") (pin "CB_33") (pinfunction "33_CB_33") (pintype "passive"))
      (node (ref "FLASH") (pin "3") (pinfunction "P$1_3") (pintype "bidirectional"))
      (node (ref "U$1") (pin "5") (pinfunction "DI_5") (pintype "bidirectional"))
    )
    (net (code "63") (name "SPI_DO") (class "Default")
      (node (ref "B1") (pin "CB_30") (pinfunction "30_CB_30") (pintype "passive"))
      (node (ref "FLASH") (pin "4") (pinfunction "P$1_4") (pintype "bidirectional"))
      (node (ref "U$1") (pin "2") (pinfunction "DO_2") (pintype "bidirectional"))
    )
    (net (code "64") (name "unconnected-(B1A-1-PadAB_1)") (class "Default")
      (node (ref "B1") (pin "AB_1") (pinfunction "1_AB_1") (pintype "passive"))
    )
    (net (code "65") (name "unconnected-(B1A-2-PadAB_2)") (class "Default")
      (node (ref "B1") (pin "AB_2") (pinfunction "2_AB_2") (pintype "passive"))
    )
    (net (code "66") (name "unconnected-(B1A-5-PadAB_5)") (class "Default")
      (node (ref "B1") (pin "AB_5") (pinfunction "5_AB_5") (pintype "passive"))
    )
    (net (code "67") (name "unconnected-(B1A-8-PadAB_8)") (class "Default")
      (node (ref "B1") (pin "AB_8") (pinfunction "8_AB_8") (pintype "passive"))
    )
    (net (code "68") (name "unconnected-(B1A-11-PadAB_11)") (class "Default")
      (node (ref "B1") (pin "AB_11") (pinfunction "11_AB_11") (pintype "passive"))
    )
    (net (code "69") (name "unconnected-(B1A-14-PadAB_14)") (class "Default")
      (node (ref "B1") (pin "AB_14") (pinfunction "14_AB_14") (pintype "passive"))
    )
    (net (code "70") (name "unconnected-(B1A-17-PadAB_17)") (class "Default")
      (node (ref "B1") (pin "AB_17") (pinfunction "17_AB_17") (pintype "passive"))
    )
    (net (code "71") (name "unconnected-(B1A-20-PadAB_20)") (class "Default")
      (node (ref "B1") (pin "AB_20") (pinfunction "20_AB_20") (pintype "passive"))
    )
    (net (code "72") (name "unconnected-(B1A-23-PadAB_23)") (class "Default")
      (node (ref "B1") (pin "AB_23") (pinfunction "23_AB_23") (pintype "passive"))
    )
    (net (code "73") (name "unconnected-(B1A-27-PadAB_27)") (class "Default")
      (node (ref "B1") (pin "AB_27") (pinfunction "27_AB_27") (pintype "passive"))
    )
    (net (code "74") (name "unconnected-(B1A-30-PadAB_30)") (class "Default")
      (node (ref "B1") (pin "AB_30") (pinfunction "30_AB_30") (pintype "passive"))
    )
    (net (code "75") (name "unconnected-(B1A-33-PadAB_33)") (class "Default")
      (node (ref "B1") (pin "AB_33") (pinfunction "33_AB_33") (pintype "passive"))
    )
    (net (code "76") (name "unconnected-(B1A-34-PadAB_34)") (class "Default")
      (node (ref "B1") (pin "AB_34") (pinfunction "34_AB_34") (pintype "passive"))
    )
    (net (code "77") (name "unconnected-(B1A-37-PadAB_37)") (class "Default")
      (node (ref "B1") (pin "AB_37") (pinfunction "37_AB_37") (pintype "passive"))
    )
    (net (code "78") (name "unconnected-(B1A-40-PadAB_40)") (class "Default")
      (node (ref "B1") (pin "AB_40") (pinfunction "40_AB_40") (pintype "passive"))
    )
    (net (code "79") (name "unconnected-(B1A-43-PadAB_43)") (class "Default")
      (node (ref "B1") (pin "AB_43") (pinfunction "43_AB_43") (pintype "passive"))
    )
    (net (code "80") (name "unconnected-(B1A-46-PadAB_46)") (class "Default")
      (node (ref "B1") (pin "AB_46") (pinfunction "46_AB_46") (pintype "passive"))
    )
    (net (code "81") (name "unconnected-(B1A-49-PadAB_49)") (class "Default")
      (node (ref "B1") (pin "AB_49") (pinfunction "49_AB_49") (pintype "passive"))
    )
    (net (code "82") (name "unconnected-(B1B-1-PadBB_1)") (class "Default")
      (node (ref "B1") (pin "BB_1") (pinfunction "1_BB_1") (pintype "passive"))
    )
    (net (code "83") (name "unconnected-(B1B-2-PadBB_2)") (class "Default")
      (node (ref "B1") (pin "BB_2") (pinfunction "2_BB_2") (pintype "passive"))
    )
    (net (code "84") (name "unconnected-(B1B-3-PadBB_3)") (class "Default")
      (node (ref "B1") (pin "BB_3") (pinfunction "3_BB_3") (pintype "passive"))
    )
    (net (code "85") (name "unconnected-(B1B-8-PadBB_8)") (class "Default")
      (node (ref "B1") (pin "BB_8") (pinfunction "8_BB_8") (pintype "passive"))
    )
    (net (code "86") (name "unconnected-(B1B-9-PadBB_9)") (class "Default")
      (node (ref "B1") (pin "BB_9") (pinfunction "9_BB_9") (pintype "passive"))
    )
    (net (code "87") (name "unconnected-(B1B-11-PadBB_11)") (class "Default")
      (node (ref "B1") (pin "BB_11") (pinfunction "11_BB_11") (pintype "passive"))
    )
    (net (code "88") (name "unconnected-(B1B-12-PadBB_12)") (class "Default")
      (node (ref "B1") (pin "BB_12") (pinfunction "12_BB_12") (pintype "passive"))
    )
    (net (code "89") (name "unconnected-(B1B-14-PadBB_14)") (class "Default")
      (node (ref "B1") (pin "BB_14") (pinfunction "14_BB_14") (pintype "passive"))
    )
    (net (code "90") (name "unconnected-(B1B-15-PadBB_15)") (class "Default")
      (node (ref "B1") (pin "BB_15") (pinfunction "15_BB_15") (pintype "passive"))
    )
    (net (code "91") (name "unconnected-(B1B-17-PadBB_17)") (class "Default")
      (node (ref "B1") (pin "BB_17") (pinfunction "17_BB_17") (pintype "passive"))
    )
    (net (code "92") (name "unconnected-(B1B-18-PadBB_18)") (class "Default")
      (node (ref "B1") (pin "BB_18") (pinfunction "18_BB_18") (pintype "passive"))
    )
    (net (code "93") (name "unconnected-(B1B-23-PadBB_23)") (class "Default")
      (node (ref "B1") (pin "BB_23") (pinfunction "23_BB_23") (pintype "passive"))
    )
    (net (code "94") (name "unconnected-(B1B-24-PadBB_24)") (class "Default")
      (node (ref "B1") (pin "BB_24") (pinfunction "24_BB_24") (pintype "passive"))
    )
    (net (code "95") (name "unconnected-(B1B-36-PadBB_36)") (class "Default")
      (node (ref "B1") (pin "BB_36") (pinfunction "36_BB_36") (pintype "passive"))
    )
    (net (code "96") (name "unconnected-(B1B-37-PadBB_37)") (class "Default")
      (node (ref "B1") (pin "BB_37") (pinfunction "37_BB_37") (pintype "passive"))
    )
    (net (code "97") (name "unconnected-(B1B-42-PadBB_42)") (class "Default")
      (node (ref "B1") (pin "BB_42") (pinfunction "42_BB_42") (pintype "passive"))
    )
    (net (code "98") (name "unconnected-(B1B-43-PadBB_43)") (class "Default")
      (node (ref "B1") (pin "BB_43") (pinfunction "43_BB_43") (pintype "passive"))
    )
    (net (code "99") (name "unconnected-(B1B-50-PadBB_50)") (class "Default")
      (node (ref "B1") (pin "BB_50") (pinfunction "50_BB_50") (pintype "passive"))
    )
    (net (code "100") (name "unconnected-(B1C-2-PadCB_2)") (class "Default")
      (node (ref "B1") (pin "CB_2") (pinfunction "2_CB_2") (pintype "passive"))
    )
    (net (code "101") (name "unconnected-(B1C-3-PadCB_3)") (class "Default")
      (node (ref "B1") (pin "CB_3") (pinfunction "3_CB_3") (pintype "passive"))
    )
    (net (code "102") (name "unconnected-(B1C-5-PadCB_5)") (class "Default")
      (node (ref "B1") (pin "CB_5") (pinfunction "5_CB_5") (pintype "passive"))
    )
    (net (code "103") (name "unconnected-(B1C-6-PadCB_6)") (class "Default")
      (node (ref "B1") (pin "CB_6") (pinfunction "6_CB_6") (pintype "passive"))
    )
    (net (code "104") (name "unconnected-(B1C-8-PadCB_8)") (class "Default")
      (node (ref "B1") (pin "CB_8") (pinfunction "8_CB_8") (pintype "passive"))
    )
    (net (code "105") (name "unconnected-(B1C-9-PadCB_9)") (class "Default")
      (node (ref "B1") (pin "CB_9") (pinfunction "9_CB_9") (pintype "passive"))
    )
    (net (code "106") (name "unconnected-(B1C-11-PadCB_11)") (class "Default")
      (node (ref "B1") (pin "CB_11") (pinfunction "11_CB_11") (pintype "passive"))
    )
    (net (code "107") (name "unconnected-(B1C-12-PadCB_12)") (class "Default")
      (node (ref "B1") (pin "CB_12") (pinfunction "12_CB_12") (pintype "passive"))
    )
    (net (code "108") (name "unconnected-(B1C-14-PadCB_14)") (class "Default")
      (node (ref "B1") (pin "CB_14") (pinfunction "14_CB_14") (pintype "passive"))
    )
    (net (code "109") (name "unconnected-(B1C-15-PadCB_15)") (class "Default")
      (node (ref "B1") (pin "CB_15") (pinfunction "15_CB_15") (pintype "passive"))
    )
    (net (code "110") (name "unconnected-(B1C-17-PadCB_17)") (class "Default")
      (node (ref "B1") (pin "CB_17") (pinfunction "17_CB_17") (pintype "passive"))
    )
    (net (code "111") (name "unconnected-(B1C-18-PadCB_18)") (class "Default")
      (node (ref "B1") (pin "CB_18") (pinfunction "18_CB_18") (pintype "passive"))
    )
    (net (code "112") (name "unconnected-(B1C-20-PadCB_20)") (class "Default")
      (node (ref "B1") (pin "CB_20") (pinfunction "20_CB_20") (pintype "passive"))
    )
    (net (code "113") (name "unconnected-(B1C-21-PadCB_21)") (class "Default")
      (node (ref "B1") (pin "CB_21") (pinfunction "21_CB_21") (pintype "passive"))
    )
    (net (code "114") (name "unconnected-(B1C-23-PadCB_23)") (class "Default")
      (node (ref "B1") (pin "CB_23") (pinfunction "23_CB_23") (pintype "passive"))
    )
    (net (code "115") (name "unconnected-(B1C-24-PadCB_24)") (class "Default")
      (node (ref "B1") (pin "CB_24") (pinfunction "24_CB_24") (pintype "passive"))
    )
    (net (code "116") (name "unconnected-(B1C-28-PadCB_28)") (class "Default")
      (node (ref "B1") (pin "CB_28") (pinfunction "28_CB_28") (pintype "passive"))
    )
    (net (code "117") (name "unconnected-(B1C-31-PadCB_31)") (class "Default")
      (node (ref "B1") (pin "CB_31") (pinfunction "31_CB_31") (pintype "passive"))
    )
    (net (code "118") (name "unconnected-(B1C-34-PadCB_34)") (class "Default")
      (node (ref "B1") (pin "CB_34") (pinfunction "34_CB_34") (pintype "passive"))
    )
    (net (code "119") (name "unconnected-(B1C-40-PadCB_40)") (class "Default")
      (node (ref "B1") (pin "CB_40") (pinfunction "40_CB_40") (pintype "passive"))
    )
    (net (code "120") (name "unconnected-(B1C-46-PadCB_46)") (class "Default")
      (node (ref "B1") (pin "CB_46") (pinfunction "46_CB_46") (pintype "passive"))
    )
    (net (code "121") (name "unconnected-(B1C-49-PadCB_49)") (class "Default")
      (node (ref "B1") (pin "CB_49") (pinfunction "49_CB_49") (pintype "passive"))
    )
    (net (code "122") (name "unconnected-(B1D-1-PadDB_1)") (class "Default")
      (node (ref "B1") (pin "DB_1") (pinfunction "1_DB_1") (pintype "passive"))
    )
    (net (code "123") (name "unconnected-(B1D-2-PadDB_2)") (class "Default")
      (node (ref "B1") (pin "DB_2") (pinfunction "2_DB_2") (pintype "passive"))
    )
    (net (code "124") (name "unconnected-(B1D-3-PadDB_3)") (class "Default")
      (node (ref "B1") (pin "DB_3") (pinfunction "3_DB_3") (pintype "passive"))
    )
    (net (code "125") (name "unconnected-(B1D-5-PadDB_5)") (class "Default")
      (node (ref "B1") (pin "DB_5") (pinfunction "5_DB_5") (pintype "passive"))
    )
    (net (code "126") (name "unconnected-(B1D-6-PadDB_6)") (class "Default")
      (node (ref "B1") (pin "DB_6") (pinfunction "6_DB_6") (pintype "passive"))
    )
    (net (code "127") (name "unconnected-(B1D-8-PadDB_8)") (class "Default")
      (node (ref "B1") (pin "DB_8") (pinfunction "8_DB_8") (pintype "passive"))
    )
    (net (code "128") (name "unconnected-(B1D-9-PadDB_9)") (class "Default")
      (node (ref "B1") (pin "DB_9") (pinfunction "9_DB_9") (pintype "passive"))
    )
    (net (code "129") (name "unconnected-(B1D-11-PadDB_11)") (class "Default")
      (node (ref "B1") (pin "DB_11") (pinfunction "11_DB_11") (pintype "passive"))
    )
    (net (code "130") (name "unconnected-(B1D-12-PadDB_12)") (class "Default")
      (node (ref "B1") (pin "DB_12") (pinfunction "12_DB_12") (pintype "passive"))
    )
    (net (code "131") (name "unconnected-(B1D-14-PadDB_14)") (class "Default")
      (node (ref "B1") (pin "DB_14") (pinfunction "14_DB_14") (pintype "passive"))
    )
    (net (code "132") (name "unconnected-(B1D-15-PadDB_15)") (class "Default")
      (node (ref "B1") (pin "DB_15") (pinfunction "15_DB_15") (pintype "passive"))
    )
    (net (code "133") (name "unconnected-(B1D-17-PadDB_17)") (class "Default")
      (node (ref "B1") (pin "DB_17") (pinfunction "17_DB_17") (pintype "passive"))
    )
    (net (code "134") (name "unconnected-(B1D-18-PadDB_18)") (class "Default")
      (node (ref "B1") (pin "DB_18") (pinfunction "18_DB_18") (pintype "passive"))
    )
    (net (code "135") (name "unconnected-(B1D-20-PadDB_20)") (class "Default")
      (node (ref "B1") (pin "DB_20") (pinfunction "20_DB_20") (pintype "passive"))
    )
    (net (code "136") (name "unconnected-(B1D-21-PadDB_21)") (class "Default")
      (node (ref "B1") (pin "DB_21") (pinfunction "21_DB_21") (pintype "passive"))
    )
    (net (code "137") (name "unconnected-(B1D-23-PadDB_23)") (class "Default")
      (node (ref "B1") (pin "DB_23") (pinfunction "23_DB_23") (pintype "passive"))
    )
    (net (code "138") (name "unconnected-(B1D-24-PadDB_24)") (class "Default")
      (node (ref "B1") (pin "DB_24") (pinfunction "24_DB_24") (pintype "passive"))
    )
    (net (code "139") (name "unconnected-(B1D-27-PadDB_27)") (class "Default")
      (node (ref "B1") (pin "DB_27") (pinfunction "27_DB_27") (pintype "passive"))
    )
    (net (code "140") (name "unconnected-(B1D-28-PadDB_28)") (class "Default")
      (node (ref "B1") (pin "DB_28") (pinfunction "28_DB_28") (pintype "passive"))
    )
    (net (code "141") (name "unconnected-(B1D-30-PadDB_30)") (class "Default")
      (node (ref "B1") (pin "DB_30") (pinfunction "30_DB_30") (pintype "passive"))
    )
    (net (code "142") (name "unconnected-(B1D-31-PadDB_31)") (class "Default")
      (node (ref "B1") (pin "DB_31") (pinfunction "31_DB_31") (pintype "passive"))
    )
    (net (code "143") (name "unconnected-(B1D-33-PadDB_33)") (class "Default")
      (node (ref "B1") (pin "DB_33") (pinfunction "33_DB_33") (pintype "passive"))
    )
    (net (code "144") (name "unconnected-(B1D-34-PadDB_34)") (class "Default")
      (node (ref "B1") (pin "DB_34") (pinfunction "34_DB_34") (pintype "passive"))
    )
    (net (code "145") (name "unconnected-(B1D-36-PadDB_36)") (class "Default")
      (node (ref "B1") (pin "DB_36") (pinfunction "36_DB_36") (pintype "passive"))
    )
    (net (code "146") (name "unconnected-(B1D-37-PadDB_37)") (class "Default")
      (node (ref "B1") (pin "DB_37") (pinfunction "37_DB_37") (pintype "passive"))
    )
    (net (code "147") (name "unconnected-(B1D-39-PadDB_39)") (class "Default")
      (node (ref "B1") (pin "DB_39") (pinfunction "39_DB_39") (pintype "passive"))
    )
    (net (code "148") (name "unconnected-(B1D-40-PadDB_40)") (class "Default")
      (node (ref "B1") (pin "DB_40") (pinfunction "40_DB_40") (pintype "passive"))
    )
    (net (code "149") (name "unconnected-(B1D-42-PadDB_42)") (class "Default")
      (node (ref "B1") (pin "DB_42") (pinfunction "42_DB_42") (pintype "passive"))
    )
    (net (code "150") (name "unconnected-(B1D-43-PadDB_43)") (class "Default")
      (node (ref "B1") (pin "DB_43") (pinfunction "43_DB_43") (pintype "passive"))
    )
    (net (code "151") (name "unconnected-(B1D-45-PadDB_45)") (class "Default")
      (node (ref "B1") (pin "DB_45") (pinfunction "45_DB_45") (pintype "passive"))
    )
    (net (code "152") (name "unconnected-(B1D-46-PadDB_46)") (class "Default")
      (node (ref "B1") (pin "DB_46") (pinfunction "46_DB_46") (pintype "passive"))
    )
    (net (code "153") (name "unconnected-(B1D-48-PadDB_48)") (class "Default")
      (node (ref "B1") (pin "DB_48") (pinfunction "48_DB_48") (pintype "passive"))
    )
    (net (code "154") (name "unconnected-(B1D-49-PadDB_49)") (class "Default")
      (node (ref "B1") (pin "DB_49") (pinfunction "49_DB_49") (pintype "passive"))
    )
    (net (code "155") (name "unconnected-(B1D-50-PadDB_50)") (class "Default")
      (node (ref "B1") (pin "DB_50") (pinfunction "50_DB_50") (pintype "passive"))
    )
    (net (code "156") (name "unconnected-(HDMI_IN/OUT-Pad13)") (class "Default")
      (node (ref "HDMI_IN/OUT") (pin "13") (pinfunction "13_13") (pintype "passive"))
    )
    (net (code "157") (name "unconnected-(HDMI_IN/OUT-Pad14)") (class "Default")
      (node (ref "HDMI_IN/OUT") (pin "14") (pinfunction "14_14") (pintype "passive"))
    )
    (net (code "158") (name "unconnected-(HDMI_OUT-Pad13)") (class "Default")
      (node (ref "HDMI_OUT") (pin "13") (pinfunction "13_13") (pintype "passive"))
    )
    (net (code "159") (name "unconnected-(HDMI_OUT-Pad14)") (class "Default")
      (node (ref "HDMI_OUT") (pin "14") (pinfunction "14_14") (pintype "passive"))
    )
    (net (code "160") (name "unconnected-(SI514-~{CLK}-PadP$5)") (class "Default")
      (node (ref "SI514") (pin "P$5") (pinfunction "~{CLK}_P$5") (pintype "bidirectional"))
    )
    (net (code "161") (name "unconnected-(U1-CEC_A-Pad1)") (class "Default")
      (node (ref "U1") (pin "1") (pinfunction "CEC_A_1") (pintype "bidirectional"))
    )
    (net (code "162") (name "unconnected-(U1-CEC_B-Pad7)") (class "Default")
      (node (ref "U1") (pin "7") (pinfunction "CEC_B_7") (pintype "bidirectional"))
    )
    (net (code "163") (name "unconnected-(U2-CEC_A-Pad1)") (class "Default")
      (node (ref "U2") (pin "1") (pinfunction "CEC_A_1") (pintype "bidirectional"))
    )
    (net (code "164") (name "unconnected-(U2-CEC_B-Pad7)") (class "Default")
      (node (ref "U2") (pin "7") (pinfunction "CEC_B_7") (pintype "bidirectional"))
    )
  )
)
